# rf_HD.net
KiCad netlist of a schematic drawn in EAGLE
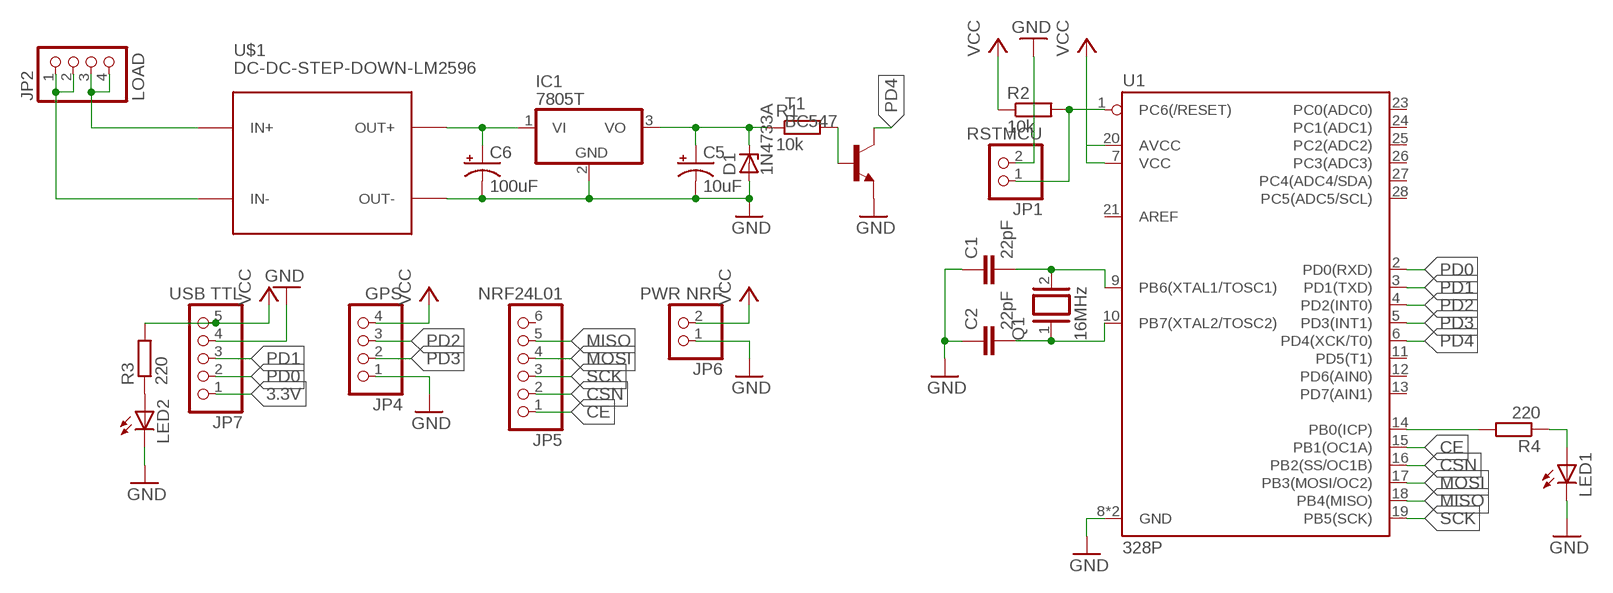
[diagram p0: schematic, sheet 1]

(export (version "E")
  (design (tool "Eeschema 10.0.6"))
  (components
    (comp (ref "C1")
      (value "22pF")
      (footprint "eagle-import:C025-024X044")
      (libsource (lib "eagle-import") (part "C-EU025-024X044"))
    )
    (comp (ref "C2")
      (value "22pF")
      (footprint "eagle-import:C025-024X044")
      (libsource (lib "eagle-import") (part "C-EU025-024X044"))
    )
    (comp (ref "C5")
      (value "10uF")
      (footprint "eagle-import:E2,5-6E")
      (libsource (lib "eagle-import") (part "CPOL-USE2,5-6E"))
    )
    (comp (ref "C6")
      (value "100uF")
      (footprint "eagle-import:E2,5-7")
      (libsource (lib "eagle-import") (part "CPOL-USE2.5-7"))
    )
    (comp (ref "D1")
      (value "1N4733A")
      (footprint "eagle-import:DO41Z10")
      (libsource (lib "eagle-import") (part "1N4728"))
    )
    (comp (ref "IC1")
      (value "7805T")
      (footprint "eagle-import:TO220H")
      (libsource (lib "eagle-import") (part "78T05"))
    )
    (comp (ref "JP1")
      (value "RSTMCU")
      (footprint "eagle-import:1X02")
      (libsource (lib "eagle-import") (part "PINHD-1X2"))
    )
    (comp (ref "JP2")
      (value "LOAD")
      (footprint "eagle-import:1X04")
      (libsource (lib "eagle-import") (part "PINHD-1X4"))
    )
    (comp (ref "JP4")
      (value "GPS")
      (footprint "eagle-import:1X04")
      (libsource (lib "eagle-import") (part "PINHD-1X4"))
    )
    (comp (ref "JP5")
      (value "NRF24L01")
      (footprint "eagle-import:1X06")
      (libsource (lib "eagle-import") (part "PINHD-1X6"))
    )
    (comp (ref "JP6")
      (value "PWR NRF")
      (footprint "eagle-import:1X02")
      (libsource (lib "eagle-import") (part "PINHD-1X2"))
    )
    (comp (ref "JP7")
      (value "USB TTL")
      (footprint "eagle-import:1X05")
      (libsource (lib "eagle-import") (part "PINHD-1X5"))
    )
    (comp (ref "LED1")
      (value "LED3MM")
      (footprint "eagle-import:LED3MM")
      (libsource (lib "eagle-import") (part "LED3MM"))
    )
    (comp (ref "LED2")
      (value "LED3MM")
      (footprint "eagle-import:LED3MM")
      (libsource (lib "eagle-import") (part "LED3MM"))
    )
    (comp (ref "Q1")
      (value "16MHz")
      (footprint "eagle-import:QS")
      (libsource (lib "eagle-import") (part "XTAL/S"))
    )
    (comp (ref "R1")
      (value "10k")
      (footprint "eagle-import:0207_12")
      (libsource (lib "eagle-import") (part "R-EU_0207/12"))
    )
    (comp (ref "R2")
      (value "10k")
      (footprint "eagle-import:0207_12")
      (libsource (lib "eagle-import") (part "R-EU_0207/12"))
    )
    (comp (ref "R3")
      (value "220")
      (footprint "eagle-import:0207_12")
      (libsource (lib "eagle-import") (part "R-EU_0207/12"))
    )
    (comp (ref "R4")
      (value "220")
      (footprint "eagle-import:0207_12")
      (libsource (lib "eagle-import") (part "R-EU_0207/12"))
    )
    (comp (ref "T1")
      (value "BC547")
      (footprint "eagle-import:TO92")
      (libsource (lib "eagle-import") (part "BC547"))
    )
    (comp (ref "U$1")
      (value "DC-DC-STEP-DOWN-LM2596")
      (footprint "eagle-import:DC-DC-STEP-DOWN-LM2596")
      (libsource (lib "eagle-import") (part "DC-DC-STEP-DOWN-LM2596"))
    )
    (comp (ref "U1")
      (value "328P")
      (footprint "eagle-import:DIP28")
      (libsource (lib "eagle-import") (part "ATMEGA328P_PDIP"))
    )
  )
  (nets
    (net (code "1") (name "3.3V") (class "Default")
      (node (ref "JP7") (pin "1") (pinfunction "1_1") (pintype "passive"))
    )
    (net (code "2") (name "CE") (class "Default")
      (node (ref "JP5") (pin "1") (pinfunction "1_1") (pintype "passive"))
      (node (ref "U1") (pin "15") (pinfunction "PB1(OC1A)_15") (pintype "bidirectional"))
    )
    (net (code "3") (name "CSN") (class "Default")
      (node (ref "JP5") (pin "2") (pinfunction "2_2") (pintype "passive"))
      (node (ref "U1") (pin "16") (pinfunction "PB2(SS/OC1B)_16") (pintype "bidirectional"))
    )
    (net (code "4") (name "GND") (class "Default")
      (node (ref "C1") (pin "1") (pinfunction "1_1") (pintype "passive"))
      (node (ref "C2") (pin "1") (pinfunction "1_1") (pintype "passive"))
      (node (ref "C5") (pin "-") (pinfunction "-_-") (pintype "passive"))
      (node (ref "C6") (pin "-") (pinfunction "-_-") (pintype "passive"))
      (node (ref "D1") (pin "A") (pinfunction "A_A") (pintype "passive"))
      (node (ref "IC1") (pin "2") (pinfunction "GND_2") (pintype "passive"))
      (node (ref "JP1") (pin "2") (pinfunction "2_2") (pintype "passive"))
      (node (ref "JP4") (pin "1") (pinfunction "1_1") (pintype "passive"))
      (node (ref "JP6") (pin "1") (pinfunction "1_1") (pintype "passive"))
      (node (ref "JP7") (pin "4") (pinfunction "4_4") (pintype "passive"))
      (node (ref "LED1") (pin "K") (pinfunction "C_K") (pintype "passive"))
      (node (ref "LED2") (pin "K") (pinfunction "C_K") (pintype "passive"))
      (node (ref "T1") (pin "1") (pinfunction "E_1") (pintype "passive"))
      (node (ref "U$1") (pin "OUT-") (pinfunction "OUT-_OUT-") (pintype "bidirectional"))
      (node (ref "U1") (pin "22") (pinfunction "GND_22") (pintype "bidirectional"))
      (node (ref "U1") (pin "8") (pinfunction "GND_8") (pintype "bidirectional"))
    )
    (net (code "5") (name "MISO") (class "Default")
      (node (ref "JP5") (pin "5") (pinfunction "5_5") (pintype "passive"))
      (node (ref "U1") (pin "18") (pinfunction "PB4(MISO)_18") (pintype "bidirectional"))
    )
    (net (code "6") (name "MOSI") (class "Default")
      (node (ref "JP5") (pin "4") (pinfunction "4_4") (pintype "passive"))
      (node (ref "U1") (pin "17") (pinfunction "PB3(MOSI/OC2)_17") (pintype "bidirectional"))
    )
    (net (code "7") (name "Net-(IC1-VI)") (class "Default")
      (node (ref "C6") (pin "+") (pinfunction "+_+") (pintype "passive"))
      (node (ref "IC1") (pin "1") (pinfunction "VI_1") (pintype "input"))
      (node (ref "U$1") (pin "OUT+") (pinfunction "OUT+_OUT+") (pintype "bidirectional"))
    )
    (net (code "8") (name "Net-(IC1-VO)") (class "Default")
      (node (ref "C5") (pin "+") (pinfunction "+_+") (pintype "passive"))
      (node (ref "D1") (pin "C") (pinfunction "C_C") (pintype "passive"))
      (node (ref "IC1") (pin "3") (pinfunction "VO_3") (pintype "passive"))
      (node (ref "R1") (pin "1") (pinfunction "1_1") (pintype "passive"))
    )
    (net (code "9") (name "Net-(JP2-Pad1)") (class "Default")
      (node (ref "JP2") (pin "1") (pinfunction "1_1") (pintype "passive"))
      (node (ref "JP2") (pin "2") (pinfunction "2_2") (pintype "passive"))
      (node (ref "U$1") (pin "IN-") (pinfunction "IN-_IN-") (pintype "bidirectional"))
    )
    (net (code "10") (name "Net-(JP2-Pad3)") (class "Default")
      (node (ref "JP2") (pin "3") (pinfunction "3_3") (pintype "passive"))
      (node (ref "JP2") (pin "4") (pinfunction "4_4") (pintype "passive"))
      (node (ref "U$1") (pin "IN+") (pinfunction "IN+_IN+") (pintype "bidirectional"))
    )
    (net (code "11") (name "Net-(LED1-PadA)") (class "Default")
      (node (ref "LED1") (pin "A") (pinfunction "A_A") (pintype "passive"))
      (node (ref "R4") (pin "1") (pinfunction "1_1") (pintype "passive"))
    )
    (net (code "12") (name "Net-(LED2-PadA)") (class "Default")
      (node (ref "LED2") (pin "A") (pinfunction "A_A") (pintype "passive"))
      (node (ref "R3") (pin "1") (pinfunction "1_1") (pintype "passive"))
    )
    (net (code "13") (name "Net-(T1-B)") (class "Default")
      (node (ref "R1") (pin "2") (pinfunction "2_2") (pintype "passive"))
      (node (ref "T1") (pin "2") (pinfunction "B_2") (pintype "passive"))
    )
    (net (code "14") (name "Net-(U1-PB0(ICP))") (class "Default")
      (node (ref "R4") (pin "2") (pinfunction "2_2") (pintype "passive"))
      (node (ref "U1") (pin "14") (pinfunction "PB0(ICP)_14") (pintype "bidirectional"))
    )
    (net (code "15") (name "Net-(U1-PB6(XTAL1{slash}TOSC1))") (class "Default")
      (node (ref "C1") (pin "2") (pinfunction "2_2") (pintype "passive"))
      (node (ref "Q1") (pin "2") (pinfunction "2_2") (pintype "passive"))
      (node (ref "U1") (pin "9") (pinfunction "PB6(XTAL1/TOSC1)_9") (pintype "bidirectional"))
    )
    (net (code "16") (name "Net-(U1-PB7(XTAL2{slash}TOSC2))") (class "Default")
      (node (ref "C2") (pin "2") (pinfunction "2_2") (pintype "passive"))
      (node (ref "Q1") (pin "1") (pinfunction "1_1") (pintype "passive"))
      (node (ref "U1") (pin "10") (pinfunction "PB7(XTAL2/TOSC2)_10") (pintype "bidirectional"))
    )
    (net (code "17") (name "Net-(U1-PC6({slash}RESET))") (class "Default")
      (node (ref "JP1") (pin "1") (pinfunction "1_1") (pintype "passive"))
      (node (ref "R2") (pin "2") (pinfunction "2_2") (pintype "passive"))
      (node (ref "U1") (pin "1") (pinfunction "PC6(/RESET)_1") (pintype "bidirectional"))
    )
    (net (code "18") (name "PD0") (class "Default")
      (node (ref "JP7") (pin "2") (pinfunction "2_2") (pintype "passive"))
      (node (ref "U1") (pin "2") (pinfunction "PD0(RXD)_2") (pintype "bidirectional"))
    )
    (net (code "19") (name "PD1") (class "Default")
      (node (ref "JP7") (pin "3") (pinfunction "3_3") (pintype "passive"))
      (node (ref "U1") (pin "3") (pinfunction "PD1(TXD)_3") (pintype "bidirectional"))
    )
    (net (code "20") (name "PD2") (class "Default")
      (node (ref "JP4") (pin "3") (pinfunction "3_3") (pintype "passive"))
      (node (ref "U1") (pin "4") (pinfunction "PD2(INT0)_4") (pintype "bidirectional"))
    )
    (net (code "21") (name "PD3") (class "Default")
      (node (ref "JP4") (pin "2") (pinfunction "2_2") (pintype "passive"))
      (node (ref "U1") (pin "5") (pinfunction "PD3(INT1)_5") (pintype "bidirectional"))
    )
    (net (code "22") (name "PD4") (class "Default")
      (node (ref "T1") (pin "3") (pinfunction "C_3") (pintype "passive"))
      (node (ref "U1") (pin "6") (pinfunction "PD4(XCK/T0)_6") (pintype "bidirectional"))
    )
    (net (code "23") (name "SCK") (class "Default")
      (node (ref "JP5") (pin "3") (pinfunction "3_3") (pintype "passive"))
      (node (ref "U1") (pin "19") (pinfunction "PB5(SCK)_19") (pintype "bidirectional"))
    )
    (net (code "24") (name "VCC") (class "Default")
      (node (ref "JP4") (pin "4") (pinfunction "4_4") (pintype "passive"))
      (node (ref "JP6") (pin "2") (pinfunction "2_2") (pintype "passive"))
      (node (ref "JP7") (pin "5") (pinfunction "5_5") (pintype "passive"))
      (node (ref "R2") (pin "1") (pinfunction "1_1") (pintype "passive"))
      (node (ref "R3") (pin "2") (pinfunction "2_2") (pintype "passive"))
      (node (ref "U1") (pin "20") (pinfunction "AVCC_20") (pintype "bidirectional"))
      (node (ref "U1") (pin "7") (pinfunction "VCC_7") (pintype "bidirectional"))
    )
    (net (code "25") (name "unconnected-(JP5-Pad6)") (class "Default")
      (node (ref "JP5") (pin "6") (pinfunction "6_6") (pintype "passive"))
    )
    (net (code "26") (name "unconnected-(U1-AREF-Pad21)") (class "Default")
      (node (ref "U1") (pin "21") (pinfunction "AREF_21") (pintype "bidirectional"))
    )
    (net (code "27") (name "unconnected-(U1-PC0(ADC0)-Pad23)") (class "Default")
      (node (ref "U1") (pin "23") (pinfunction "PC0(ADC0)_23") (pintype "bidirectional"))
    )
    (net (code "28") (name "unconnected-(U1-PC1(ADC1)-Pad24)") (class "Default")
      (node (ref "U1") (pin "24") (pinfunction "PC1(ADC1)_24") (pintype "bidirectional"))
    )
    (net (code "29") (name "unconnected-(U1-PC2(ADC2)-Pad25)") (class "Default")
      (node (ref "U1") (pin "25") (pinfunction "PC2(ADC2)_25") (pintype "bidirectional"))
    )
    (net (code "30") (name "unconnected-(U1-PC3(ADC3)-Pad26)") (class "Default")
      (node (ref "U1") (pin "26") (pinfunction "PC3(ADC3)_26") (pintype "bidirectional"))
    )
    (net (code "31") (name "unconnected-(U1-PC4(ADC4{slash}SDA)-Pad27)") (class "Default")
      (node (ref "U1") (pin "27") (pinfunction "PC4(ADC4/SDA)_27") (pintype "bidirectional"))
    )
    (net (code "32") (name "unconnected-(U1-PC5(ADC5{slash}SCL)-Pad28)") (class "Default")
      (node (ref "U1") (pin "28") (pinfunction "PC5(ADC5/SCL)_28") (pintype "bidirectional"))
    )
    (net (code "33") (name "unconnected-(U1-PD5(T1)-Pad11)") (class "Default")
      (node (ref "U1") (pin "11") (pinfunction "PD5(T1)_11") (pintype "bidirectional"))
    )
    (net (code "34") (name "unconnected-(U1-PD6(AIN0)-Pad12)") (class "Default")
      (node (ref "U1") (pin "12") (pinfunction "PD6(AIN0)_12") (pintype "bidirectional"))
    )
    (net (code "35") (name "unconnected-(U1-PD7(AIN1)-Pad13)") (class "Default")
      (node (ref "U1") (pin "13") (pinfunction "PD7(AIN1)_13") (pintype "bidirectional"))
    )
  )
)
